# Kintex7_disp_out_hdmi.net
KiCad netlist of a schematic drawn in EAGLE
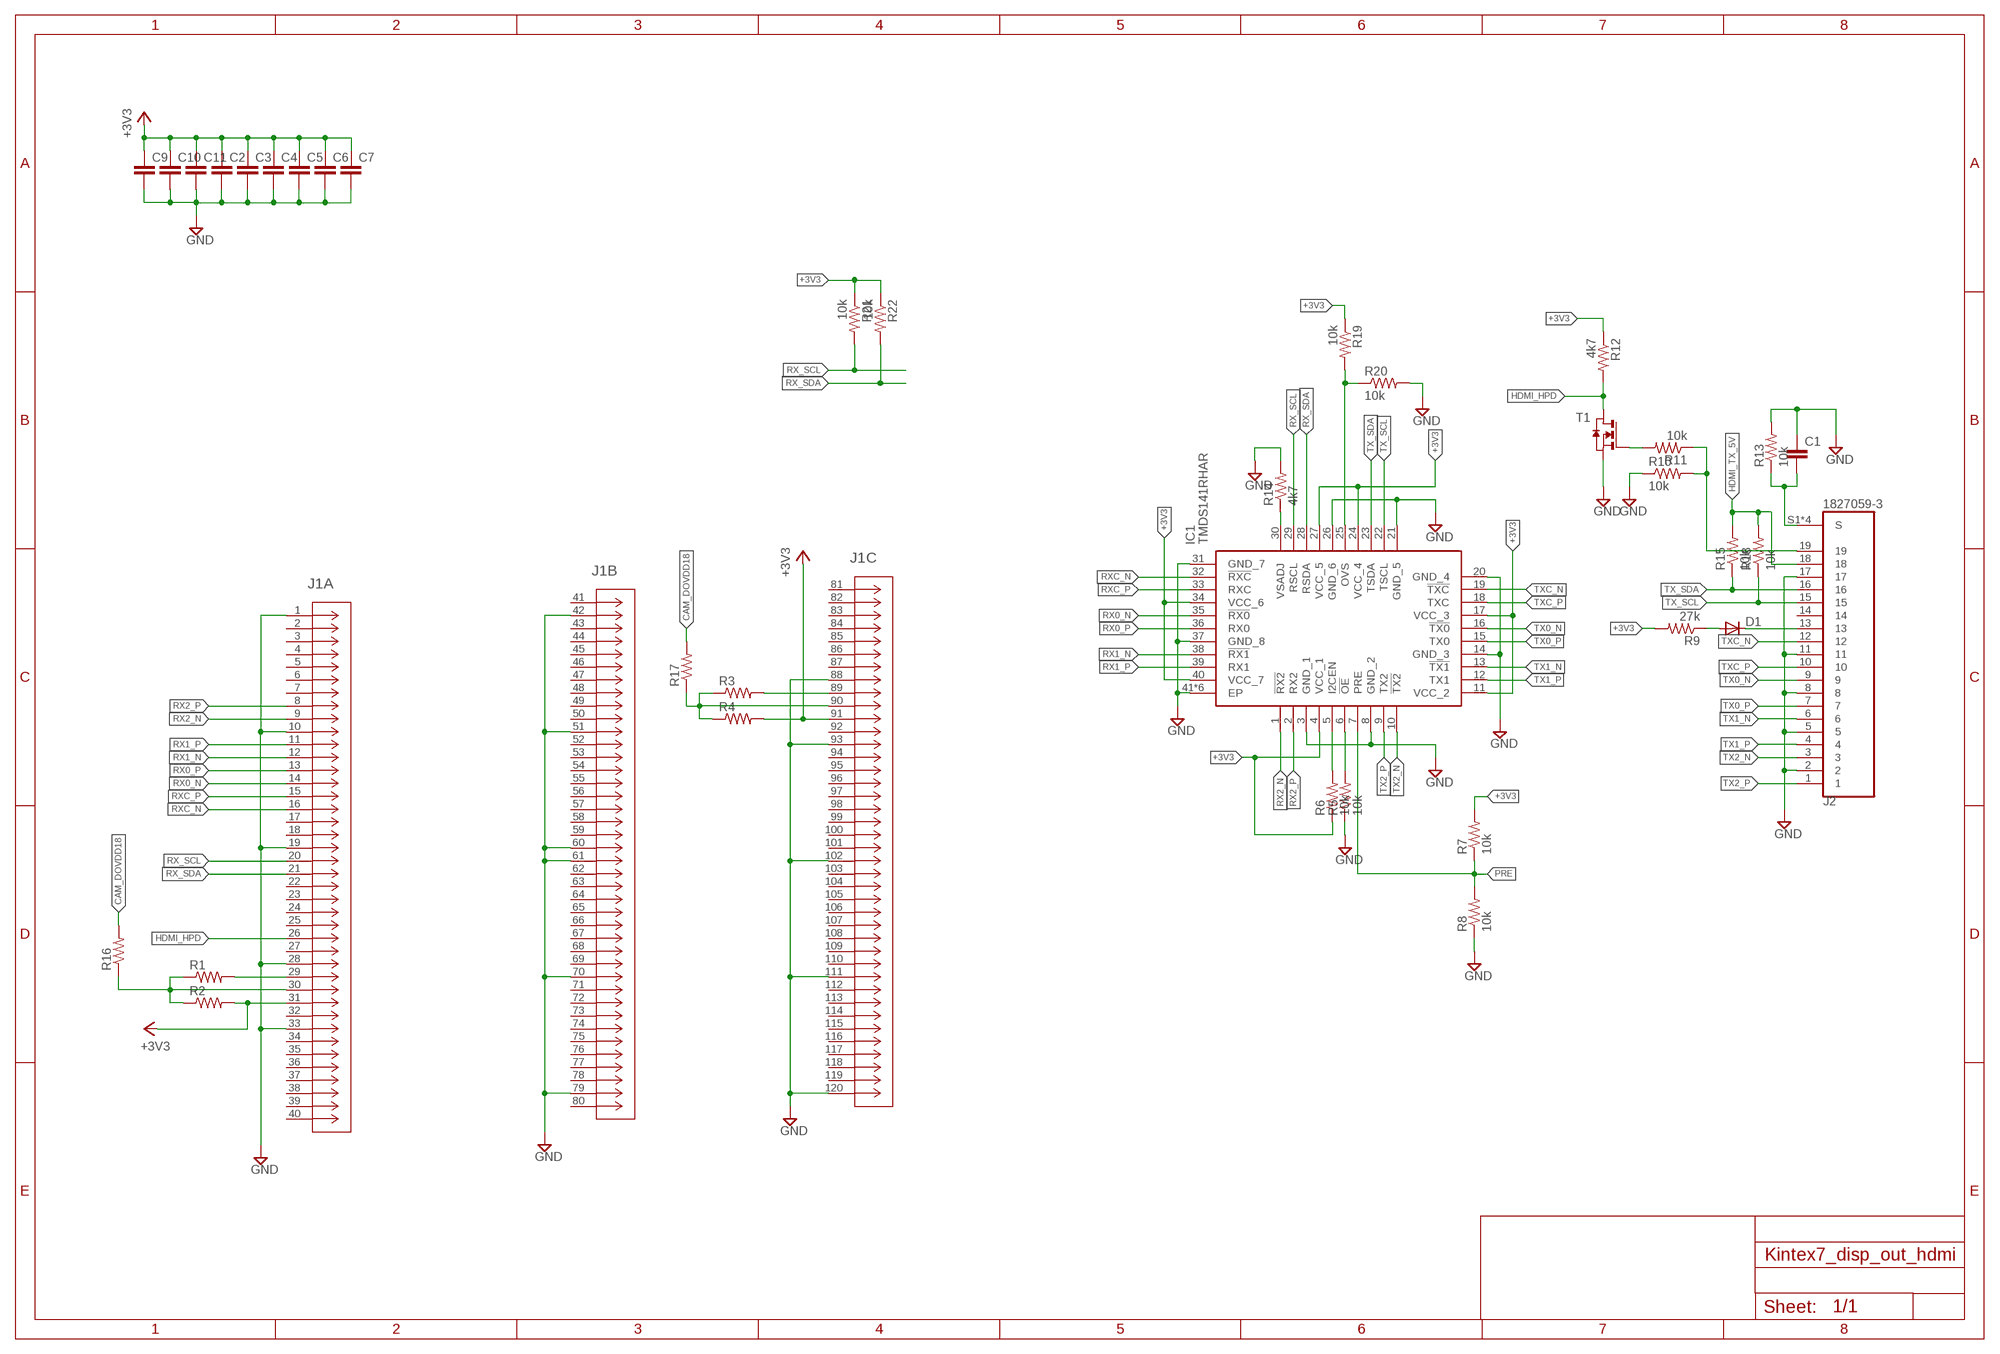
[diagram p0: schematic, sheet 1]

(export (version "E")
  (design (tool "Eeschema 10.0.6"))
  (components
    (comp (ref "C1")
      (value "C-EUC0603")
      (footprint "eagle-import:C0603")
      (libsource (lib "eagle-import") (part "C-EUC0603"))
    )
    (comp (ref "C2")
      (value "C-EUC0603")
      (footprint "eagle-import:C0603")
      (libsource (lib "eagle-import") (part "C-EUC0603"))
    )
    (comp (ref "C3")
      (value "C-EUC0603")
      (footprint "eagle-import:C0603")
      (libsource (lib "eagle-import") (part "C-EUC0603"))
    )
    (comp (ref "C4")
      (value "C-EUC0603")
      (footprint "eagle-import:C0603")
      (libsource (lib "eagle-import") (part "C-EUC0603"))
    )
    (comp (ref "C5")
      (value "C-EUC0603")
      (footprint "eagle-import:C0603")
      (libsource (lib "eagle-import") (part "C-EUC0603"))
    )
    (comp (ref "C6")
      (value "C-EUC0603")
      (footprint "eagle-import:C0603")
      (libsource (lib "eagle-import") (part "C-EUC0603"))
    )
    (comp (ref "C7")
      (value "C-EUC0603")
      (footprint "eagle-import:C0603")
      (libsource (lib "eagle-import") (part "C-EUC0603"))
    )
    (comp (ref "C9")
      (value "C-EUC0603")
      (footprint "eagle-import:C0603")
      (libsource (lib "eagle-import") (part "C-EUC0603"))
    )
    (comp (ref "C10")
      (value "C-EUC0603")
      (footprint "eagle-import:C0603")
      (libsource (lib "eagle-import") (part "C-EUC0603"))
    )
    (comp (ref "C11")
      (value "C-EUC0603")
      (footprint "eagle-import:C0603")
      (libsource (lib "eagle-import") (part "C-EUC0603"))
    )
    (comp (ref "D1")
      (value "DIODE-MINIMELF")
      (footprint "eagle-import:MINIMELF")
      (libsource (lib "eagle-import") (part "DIODE-MINIMELF"))
    )
    (comp (ref "IC1")
      (value "TMDS141RHAR")
      (footprint "eagle-import:QFN50P600X600X100-41N")
      (fields (field (name "RS_PART_NUMBER") "8124195P"))
      (libsource (lib "eagle-import") (part "TMDS141RHAR"))
    )
    (comp (ref "J1")
      (value "5177985-5")
      (footprint "eagle-import:CONN_5177985-5")
      (libsource (lib "eagle-import") (part "5177985-5"))
    )
    (comp (ref "J2")
      (value "1827059-3")
      (footprint "eagle-import:TE_1827059-3")
      (fields (field (name "MF") "TE Connectivity"))
      (libsource (lib "eagle-import") (part "1827059-3"))
    )
    (comp (ref "R1")
      (value "R-US_R0805")
      (footprint "eagle-import:R0805")
      (libsource (lib "eagle-import") (part "R-US_R0805"))
    )
    (comp (ref "R2")
      (value "R-US_R0805")
      (footprint "eagle-import:R0805")
      (libsource (lib "eagle-import") (part "R-US_R0805"))
    )
    (comp (ref "R3")
      (value "R-US_R0805")
      (footprint "eagle-import:R0805")
      (libsource (lib "eagle-import") (part "R-US_R0805"))
    )
    (comp (ref "R4")
      (value "R-US_R0805")
      (footprint "eagle-import:R0805")
      (libsource (lib "eagle-import") (part "R-US_R0805"))
    )
    (comp (ref "R5")
      (value "10k")
      (footprint "eagle-import:R0805")
      (libsource (lib "eagle-import") (part "R-US_R0805"))
    )
    (comp (ref "R6")
      (value "10k")
      (footprint "eagle-import:R0805")
      (libsource (lib "eagle-import") (part "R-US_R0805"))
    )
    (comp (ref "R7")
      (value "10k")
      (footprint "eagle-import:R0805")
      (libsource (lib "eagle-import") (part "R-US_R0805"))
    )
    (comp (ref "R8")
      (value "10k")
      (footprint "eagle-import:R0805")
      (libsource (lib "eagle-import") (part "R-US_R0805"))
    )
    (comp (ref "R9")
      (value "27k")
      (footprint "eagle-import:R0805")
      (libsource (lib "eagle-import") (part "R-US_R0805"))
    )
    (comp (ref "R10")
      (value "10k")
      (footprint "eagle-import:R0805")
      (libsource (lib "eagle-import") (part "R-US_R0805"))
    )
    (comp (ref "R11")
      (value "10k")
      (footprint "eagle-import:R0805")
      (libsource (lib "eagle-import") (part "R-US_R0805"))
    )
    (comp (ref "R12")
      (value "4k7")
      (footprint "eagle-import:R0805")
      (libsource (lib "eagle-import") (part "R-US_R0805"))
    )
    (comp (ref "R13")
      (value "10k")
      (footprint "eagle-import:R0805")
      (libsource (lib "eagle-import") (part "R-US_R0805"))
    )
    (comp (ref "R14")
      (value "4k7")
      (footprint "eagle-import:R0805")
      (libsource (lib "eagle-import") (part "R-US_R0805"))
    )
    (comp (ref "R15")
      (value "10k")
      (footprint "eagle-import:R0805")
      (libsource (lib "eagle-import") (part "R-US_R0805"))
    )
    (comp (ref "R16")
      (value "R-US_R0805")
      (footprint "eagle-import:R0805")
      (libsource (lib "eagle-import") (part "R-US_R0805"))
    )
    (comp (ref "R17")
      (value "R-US_R0805")
      (footprint "eagle-import:R0805")
      (libsource (lib "eagle-import") (part "R-US_R0805"))
    )
    (comp (ref "R18")
      (value "10k")
      (footprint "eagle-import:R0805")
      (libsource (lib "eagle-import") (part "R-US_R0805"))
    )
    (comp (ref "R19")
      (value "10k")
      (footprint "eagle-import:R0805")
      (libsource (lib "eagle-import") (part "R-US_R0805"))
    )
    (comp (ref "R20")
      (value "10k")
      (footprint "eagle-import:R0805")
      (libsource (lib "eagle-import") (part "R-US_R0805"))
    )
    (comp (ref "R21")
      (value "10k")
      (footprint "eagle-import:R0805")
      (libsource (lib "eagle-import") (part "R-US_R0805"))
    )
    (comp (ref "R22")
      (value "10k")
      (footprint "eagle-import:R0805")
      (libsource (lib "eagle-import") (part "R-US_R0805"))
    )
    (comp (ref "T1")
      (value "NMOSSOT23")
      (footprint "eagle-import:SOT-23")
      (libsource (lib "eagle-import") (part "NMOSSOT23"))
    )
  )
  (nets
    (net (code "1") (name "+3V3") (class "Default")
      (node (ref "C10") (pin "1") (pinfunction "1_1") (pintype "passive"))
      (node (ref "C11") (pin "1") (pinfunction "1_1") (pintype "passive"))
      (node (ref "C2") (pin "1") (pinfunction "1_1") (pintype "passive"))
      (node (ref "C3") (pin "1") (pinfunction "1_1") (pintype "passive"))
      (node (ref "C4") (pin "1") (pinfunction "1_1") (pintype "passive"))
      (node (ref "C5") (pin "1") (pinfunction "1_1") (pintype "passive"))
      (node (ref "C6") (pin "1") (pinfunction "1_1") (pintype "passive"))
      (node (ref "C7") (pin "1") (pinfunction "1_1") (pintype "passive"))
      (node (ref "C9") (pin "1") (pinfunction "1_1") (pintype "passive"))
      (node (ref "IC1") (pin "11") (pinfunction "VCC_2_11") (pintype "bidirectional"))
      (node (ref "IC1") (pin "17") (pinfunction "VCC_3_17") (pintype "bidirectional"))
      (node (ref "IC1") (pin "24") (pinfunction "VCC_4_24") (pintype "bidirectional"))
      (node (ref "IC1") (pin "27") (pinfunction "VCC_5_27") (pintype "bidirectional"))
      (node (ref "IC1") (pin "34") (pinfunction "VCC_6_34") (pintype "bidirectional"))
      (node (ref "IC1") (pin "4") (pinfunction "VCC_1_4") (pintype "bidirectional"))
      (node (ref "IC1") (pin "40") (pinfunction "VCC_7_40") (pintype "bidirectional"))
      (node (ref "J1") (pin "31") (pinfunction "31_31") (pintype "passive"))
      (node (ref "J1") (pin "91") (pinfunction "91_91") (pintype "passive"))
      (node (ref "R12") (pin "1") (pinfunction "1_1") (pintype "passive"))
      (node (ref "R19") (pin "1") (pinfunction "1_1") (pintype "passive"))
      (node (ref "R2") (pin "2") (pinfunction "2_2") (pintype "passive"))
      (node (ref "R21") (pin "1") (pinfunction "1_1") (pintype "passive"))
      (node (ref "R22") (pin "1") (pinfunction "1_1") (pintype "passive"))
      (node (ref "R4") (pin "2") (pinfunction "2_2") (pintype "passive"))
      (node (ref "R6") (pin "1") (pinfunction "1_1") (pintype "passive"))
      (node (ref "R7") (pin "2") (pinfunction "2_2") (pintype "passive"))
      (node (ref "R9") (pin "2") (pinfunction "2_2") (pintype "passive"))
    )
    (net (code "2") (name "CAM_DOVDD18") (class "Default")
      (node (ref "R16") (pin "2") (pinfunction "2_2") (pintype "passive"))
      (node (ref "R17") (pin "2") (pinfunction "2_2") (pintype "passive"))
    )
    (net (code "3") (name "GND") (class "Default")
      (node (ref "C1") (pin "1") (pinfunction "1_1") (pintype "passive"))
      (node (ref "C10") (pin "2") (pinfunction "2_2") (pintype "passive"))
      (node (ref "C11") (pin "2") (pinfunction "2_2") (pintype "passive"))
      (node (ref "C2") (pin "2") (pinfunction "2_2") (pintype "passive"))
      (node (ref "C3") (pin "2") (pinfunction "2_2") (pintype "passive"))
      (node (ref "C4") (pin "2") (pinfunction "2_2") (pintype "passive"))
      (node (ref "C5") (pin "2") (pinfunction "2_2") (pintype "passive"))
      (node (ref "C6") (pin "2") (pinfunction "2_2") (pintype "passive"))
      (node (ref "C7") (pin "2") (pinfunction "2_2") (pintype "passive"))
      (node (ref "C9") (pin "2") (pinfunction "2_2") (pintype "passive"))
      (node (ref "IC1") (pin "14") (pinfunction "GND_3_14") (pintype "bidirectional"))
      (node (ref "IC1") (pin "20") (pinfunction "GND_4_20") (pintype "bidirectional"))
      (node (ref "IC1") (pin "21") (pinfunction "GND_5_21") (pintype "bidirectional"))
      (node (ref "IC1") (pin "26") (pinfunction "GND_6_26") (pintype "bidirectional"))
      (node (ref "IC1") (pin "3") (pinfunction "GND_1_3") (pintype "bidirectional"))
      (node (ref "IC1") (pin "31") (pinfunction "GND_7_31") (pintype "bidirectional"))
      (node (ref "IC1") (pin "37") (pinfunction "GND_8_37") (pintype "bidirectional"))
      (node (ref "IC1") (pin "41") (pinfunction "EP_41") (pintype "bidirectional"))
      (node (ref "IC1") (pin "8") (pinfunction "GND_2_8") (pintype "bidirectional"))
      (node (ref "IC1") (pin "P$1") (pinfunction "EP_P$1") (pintype "bidirectional"))
      (node (ref "IC1") (pin "P$2") (pinfunction "EP_P$2") (pintype "bidirectional"))
      (node (ref "IC1") (pin "P$3") (pinfunction "EP_P$3") (pintype "bidirectional"))
      (node (ref "IC1") (pin "P$4") (pinfunction "EP_P$4") (pintype "bidirectional"))
      (node (ref "IC1") (pin "P$5") (pinfunction "EP_P$5") (pintype "bidirectional"))
      (node (ref "J1") (pin "1") (pinfunction "1_1") (pintype "passive"))
      (node (ref "J1") (pin "10") (pinfunction "10_10") (pintype "passive"))
      (node (ref "J1") (pin "102") (pinfunction "102_102") (pintype "passive"))
      (node (ref "J1") (pin "111") (pinfunction "111_111") (pintype "passive"))
      (node (ref "J1") (pin "120") (pinfunction "120_120") (pintype "passive"))
      (node (ref "J1") (pin "19") (pinfunction "19_19") (pintype "passive"))
      (node (ref "J1") (pin "28") (pinfunction "28_28") (pintype "passive"))
      (node (ref "J1") (pin "33") (pinfunction "33_33") (pintype "passive"))
      (node (ref "J1") (pin "42") (pinfunction "42_42") (pintype "passive"))
      (node (ref "J1") (pin "51") (pinfunction "51_51") (pintype "passive"))
      (node (ref "J1") (pin "60") (pinfunction "60_60") (pintype "passive"))
      (node (ref "J1") (pin "61") (pinfunction "61_61") (pintype "passive"))
      (node (ref "J1") (pin "70") (pinfunction "70_70") (pintype "passive"))
      (node (ref "J1") (pin "79") (pinfunction "79_79") (pintype "passive"))
      (node (ref "J1") (pin "88") (pinfunction "88_88") (pintype "passive"))
      (node (ref "J1") (pin "93") (pinfunction "93_93") (pintype "passive"))
      (node (ref "J2") (pin "11") (pinfunction "11_11") (pintype "passive"))
      (node (ref "J2") (pin "17") (pinfunction "17_17") (pintype "passive"))
      (node (ref "J2") (pin "2") (pinfunction "2_2") (pintype "passive"))
      (node (ref "J2") (pin "5") (pinfunction "5_5") (pintype "passive"))
      (node (ref "J2") (pin "8") (pinfunction "8_8") (pintype "passive"))
      (node (ref "R10") (pin "1") (pinfunction "1_1") (pintype "passive"))
      (node (ref "R13") (pin "2") (pinfunction "2_2") (pintype "passive"))
      (node (ref "R14") (pin "2") (pinfunction "2_2") (pintype "passive"))
      (node (ref "R20") (pin "2") (pinfunction "2_2") (pintype "passive"))
      (node (ref "R5") (pin "1") (pinfunction "1_1") (pintype "passive"))
      (node (ref "R8") (pin "1") (pinfunction "1_1") (pintype "passive"))
      (node (ref "T1") (pin "2") (pinfunction "S_2") (pintype "passive"))
    )
    (net (code "4") (name "HDMI_HPD") (class "Default")
      (node (ref "J1") (pin "26") (pinfunction "26_26") (pintype "passive"))
      (node (ref "R12") (pin "2") (pinfunction "2_2") (pintype "passive"))
      (node (ref "T1") (pin "1") (pinfunction "D_1") (pintype "passive"))
    )
    (net (code "5") (name "HDMI_TX_5V") (class "Default")
      (node (ref "J2") (pin "18") (pinfunction "18_18") (pintype "passive"))
      (node (ref "R15") (pin "2") (pinfunction "2_2") (pintype "passive"))
      (node (ref "R18") (pin "2") (pinfunction "2_2") (pintype "passive"))
    )
    (net (code "6") (name "Net-(C1-Pad2)") (class "Default")
      (node (ref "C1") (pin "2") (pinfunction "2_2") (pintype "passive"))
      (node (ref "J2") (pin "S1") (pinfunction "S_S1") (pintype "passive"))
      (node (ref "J2") (pin "S2") (pinfunction "S_S2") (pintype "passive"))
      (node (ref "J2") (pin "S3") (pinfunction "S_S3") (pintype "passive"))
      (node (ref "J2") (pin "S4") (pinfunction "S_S4") (pintype "passive"))
      (node (ref "R13") (pin "1") (pinfunction "1_1") (pintype "passive"))
    )
    (net (code "7") (name "Net-(D1-PadA)") (class "Default")
      (node (ref "D1") (pin "A") (pinfunction "A_A") (pintype "passive"))
      (node (ref "R9") (pin "1") (pinfunction "1_1") (pintype "passive"))
    )
    (net (code "8") (name "Net-(D1-PadC)") (class "Default")
      (node (ref "D1") (pin "C") (pinfunction "C_C") (pintype "passive"))
      (node (ref "J2") (pin "13") (pinfunction "13_13") (pintype "passive"))
    )
    (net (code "9") (name "Net-(IC1-I2CEN)") (class "Default")
      (node (ref "IC1") (pin "5") (pinfunction "I2CEN_5") (pintype "bidirectional"))
      (node (ref "R6") (pin "2") (pinfunction "2_2") (pintype "passive"))
    )
    (net (code "10") (name "Net-(IC1-OVS)") (class "Default")
      (node (ref "IC1") (pin "25") (pinfunction "OVS_25") (pintype "bidirectional"))
      (node (ref "R19") (pin "2") (pinfunction "2_2") (pintype "passive"))
      (node (ref "R20") (pin "1") (pinfunction "1_1") (pintype "passive"))
    )
    (net (code "11") (name "Net-(IC1-VSADJ)") (class "Default")
      (node (ref "IC1") (pin "30") (pinfunction "VSADJ_30") (pintype "bidirectional"))
      (node (ref "R14") (pin "1") (pinfunction "1_1") (pintype "passive"))
    )
    (net (code "12") (name "Net-(IC1-~{OE})") (class "Default")
      (node (ref "IC1") (pin "6") (pinfunction "~{OE}_6") (pintype "bidirectional"))
      (node (ref "R5") (pin "2") (pinfunction "2_2") (pintype "passive"))
    )
    (net (code "13") (name "Net-(J1-Pad29)") (class "Default")
      (node (ref "J1") (pin "29") (pinfunction "29_29") (pintype "passive"))
      (node (ref "R1") (pin "2") (pinfunction "2_2") (pintype "passive"))
    )
    (net (code "14") (name "Net-(J1-Pad30)") (class "Default")
      (node (ref "J1") (pin "30") (pinfunction "30_30") (pintype "passive"))
      (node (ref "R1") (pin "1") (pinfunction "1_1") (pintype "passive"))
      (node (ref "R16") (pin "1") (pinfunction "1_1") (pintype "passive"))
      (node (ref "R2") (pin "1") (pinfunction "1_1") (pintype "passive"))
    )
    (net (code "15") (name "Net-(J1-Pad89)") (class "Default")
      (node (ref "J1") (pin "89") (pinfunction "89_89") (pintype "passive"))
      (node (ref "R3") (pin "2") (pinfunction "2_2") (pintype "passive"))
    )
    (net (code "16") (name "Net-(J1-Pad90)") (class "Default")
      (node (ref "J1") (pin "90") (pinfunction "90_90") (pintype "passive"))
      (node (ref "R17") (pin "1") (pinfunction "1_1") (pintype "passive"))
      (node (ref "R3") (pin "1") (pinfunction "1_1") (pintype "passive"))
      (node (ref "R4") (pin "1") (pinfunction "1_1") (pintype "passive"))
    )
    (net (code "17") (name "Net-(J2-Pad19)") (class "Default")
      (node (ref "J2") (pin "19") (pinfunction "19_19") (pintype "passive"))
      (node (ref "R10") (pin "2") (pinfunction "2_2") (pintype "passive"))
      (node (ref "R11") (pin "1") (pinfunction "1_1") (pintype "passive"))
    )
    (net (code "18") (name "Net-(T1-G)") (class "Default")
      (node (ref "R11") (pin "2") (pinfunction "2_2") (pintype "passive"))
      (node (ref "T1") (pin "3") (pinfunction "G_3") (pintype "passive"))
    )
    (net (code "19") (name "PRE") (class "Default")
      (node (ref "IC1") (pin "7") (pinfunction "PRE_7") (pintype "bidirectional"))
      (node (ref "R7") (pin "1") (pinfunction "1_1") (pintype "passive"))
      (node (ref "R8") (pin "2") (pinfunction "2_2") (pintype "passive"))
    )
    (net (code "20") (name "RX0_N") (class "Default")
      (node (ref "IC1") (pin "35") (pinfunction "~{RX0}_35") (pintype "bidirectional"))
      (node (ref "J1") (pin "14") (pinfunction "14_14") (pintype "passive"))
    )
    (net (code "21") (name "RX0_P") (class "Default")
      (node (ref "IC1") (pin "36") (pinfunction "RX0_36") (pintype "bidirectional"))
      (node (ref "J1") (pin "13") (pinfunction "13_13") (pintype "passive"))
    )
    (net (code "22") (name "RX1_N") (class "Default")
      (node (ref "IC1") (pin "38") (pinfunction "~{RX1}_38") (pintype "bidirectional"))
      (node (ref "J1") (pin "12") (pinfunction "12_12") (pintype "passive"))
    )
    (net (code "23") (name "RX1_P") (class "Default")
      (node (ref "IC1") (pin "39") (pinfunction "RX1_39") (pintype "bidirectional"))
      (node (ref "J1") (pin "11") (pinfunction "11_11") (pintype "passive"))
    )
    (net (code "24") (name "RX2_N") (class "Default")
      (node (ref "IC1") (pin "1") (pinfunction "~{RX2}_1") (pintype "bidirectional"))
      (node (ref "J1") (pin "9") (pinfunction "9_9") (pintype "passive"))
    )
    (net (code "25") (name "RX2_P") (class "Default")
      (node (ref "IC1") (pin "2") (pinfunction "RX2_2") (pintype "bidirectional"))
      (node (ref "J1") (pin "8") (pinfunction "8_8") (pintype "passive"))
    )
    (net (code "26") (name "RXC_N") (class "Default")
      (node (ref "IC1") (pin "32") (pinfunction "~{RXC}_32") (pintype "bidirectional"))
      (node (ref "J1") (pin "16") (pinfunction "16_16") (pintype "passive"))
    )
    (net (code "27") (name "RXC_P") (class "Default")
      (node (ref "IC1") (pin "33") (pinfunction "RXC_33") (pintype "bidirectional"))
      (node (ref "J1") (pin "15") (pinfunction "15_15") (pintype "passive"))
    )
    (net (code "28") (name "RX_SCL") (class "Default")
      (node (ref "IC1") (pin "29") (pinfunction "RSCL_29") (pintype "bidirectional"))
      (node (ref "J1") (pin "20") (pinfunction "20_20") (pintype "passive"))
      (node (ref "R21") (pin "2") (pinfunction "2_2") (pintype "passive"))
    )
    (net (code "29") (name "RX_SDA") (class "Default")
      (node (ref "IC1") (pin "28") (pinfunction "RSDA_28") (pintype "bidirectional"))
      (node (ref "J1") (pin "21") (pinfunction "21_21") (pintype "passive"))
      (node (ref "R22") (pin "2") (pinfunction "2_2") (pintype "passive"))
    )
    (net (code "30") (name "TX0_N") (class "Default")
      (node (ref "IC1") (pin "16") (pinfunction "~{TX0}_16") (pintype "bidirectional"))
      (node (ref "J2") (pin "9") (pinfunction "9_9") (pintype "passive"))
    )
    (net (code "31") (name "TX0_P") (class "Default")
      (node (ref "IC1") (pin "15") (pinfunction "TX0_15") (pintype "bidirectional"))
      (node (ref "J2") (pin "7") (pinfunction "7_7") (pintype "passive"))
    )
    (net (code "32") (name "TX1_N") (class "Default")
      (node (ref "IC1") (pin "13") (pinfunction "~{TX1}_13") (pintype "bidirectional"))
      (node (ref "J2") (pin "6") (pinfunction "6_6") (pintype "passive"))
    )
    (net (code "33") (name "TX1_P") (class "Default")
      (node (ref "IC1") (pin "12") (pinfunction "TX1_12") (pintype "bidirectional"))
      (node (ref "J2") (pin "4") (pinfunction "4_4") (pintype "passive"))
    )
    (net (code "34") (name "TX2_N") (class "Default")
      (node (ref "IC1") (pin "10") (pinfunction "~{TX2}_10") (pintype "bidirectional"))
      (node (ref "J2") (pin "3") (pinfunction "3_3") (pintype "passive"))
    )
    (net (code "35") (name "TX2_P") (class "Default")
      (node (ref "IC1") (pin "9") (pinfunction "TX2_9") (pintype "bidirectional"))
      (node (ref "J2") (pin "1") (pinfunction "1_1") (pintype "passive"))
    )
    (net (code "36") (name "TXC_N") (class "Default")
      (node (ref "IC1") (pin "19") (pinfunction "~{TXC}_19") (pintype "bidirectional"))
      (node (ref "J2") (pin "12") (pinfunction "12_12") (pintype "passive"))
    )
    (net (code "37") (name "TXC_P") (class "Default")
      (node (ref "IC1") (pin "18") (pinfunction "TXC_18") (pintype "bidirectional"))
      (node (ref "J2") (pin "10") (pinfunction "10_10") (pintype "passive"))
    )
    (net (code "38") (name "TX_SCL") (class "Default")
      (node (ref "IC1") (pin "22") (pinfunction "TSCL_22") (pintype "bidirectional"))
      (node (ref "J2") (pin "15") (pinfunction "15_15") (pintype "passive"))
      (node (ref "R18") (pin "1") (pinfunction "1_1") (pintype "passive"))
    )
    (net (code "39") (name "TX_SDA") (class "Default")
      (node (ref "IC1") (pin "23") (pinfunction "TSDA_23") (pintype "bidirectional"))
      (node (ref "J2") (pin "16") (pinfunction "16_16") (pintype "passive"))
      (node (ref "R15") (pin "1") (pinfunction "1_1") (pintype "passive"))
    )
    (net (code "40") (name "unconnected-(J1-Pad2)") (class "Default")
      (node (ref "J1") (pin "2") (pinfunction "2_2") (pintype "passive"))
    )
    (net (code "41") (name "unconnected-(J1-Pad3)") (class "Default")
      (node (ref "J1") (pin "3") (pinfunction "3_3") (pintype "passive"))
    )
    (net (code "42") (name "unconnected-(J1-Pad4)") (class "Default")
      (node (ref "J1") (pin "4") (pinfunction "4_4") (pintype "passive"))
    )
    (net (code "43") (name "unconnected-(J1-Pad5)") (class "Default")
      (node (ref "J1") (pin "5") (pinfunction "5_5") (pintype "passive"))
    )
    (net (code "44") (name "unconnected-(J1-Pad6)") (class "Default")
      (node (ref "J1") (pin "6") (pinfunction "6_6") (pintype "passive"))
    )
    (net (code "45") (name "unconnected-(J1-Pad7)") (class "Default")
      (node (ref "J1") (pin "7") (pinfunction "7_7") (pintype "passive"))
    )
    (net (code "46") (name "unconnected-(J1-Pad17)") (class "Default")
      (node (ref "J1") (pin "17") (pinfunction "17_17") (pintype "passive"))
    )
    (net (code "47") (name "unconnected-(J1-Pad18)") (class "Default")
      (node (ref "J1") (pin "18") (pinfunction "18_18") (pintype "passive"))
    )
    (net (code "48") (name "unconnected-(J1-Pad22)") (class "Default")
      (node (ref "J1") (pin "22") (pinfunction "22_22") (pintype "passive"))
    )
    (net (code "49") (name "unconnected-(J1-Pad23)") (class "Default")
      (node (ref "J1") (pin "23") (pinfunction "23_23") (pintype "passive"))
    )
    (net (code "50") (name "unconnected-(J1-Pad24)") (class "Default")
      (node (ref "J1") (pin "24") (pinfunction "24_24") (pintype "passive"))
    )
    (net (code "51") (name "unconnected-(J1-Pad25)") (class "Default")
      (node (ref "J1") (pin "25") (pinfunction "25_25") (pintype "passive"))
    )
    (net (code "52") (name "unconnected-(J1-Pad27)") (class "Default")
      (node (ref "J1") (pin "27") (pinfunction "27_27") (pintype "passive"))
    )
    (net (code "53") (name "unconnected-(J1-Pad32)") (class "Default")
      (node (ref "J1") (pin "32") (pinfunction "32_32") (pintype "passive"))
    )
    (net (code "54") (name "unconnected-(J1-Pad34)") (class "Default")
      (node (ref "J1") (pin "34") (pinfunction "34_34") (pintype "passive"))
    )
    (net (code "55") (name "unconnected-(J1-Pad35)") (class "Default")
      (node (ref "J1") (pin "35") (pinfunction "35_35") (pintype "passive"))
    )
    (net (code "56") (name "unconnected-(J1-Pad36)") (class "Default")
      (node (ref "J1") (pin "36") (pinfunction "36_36") (pintype "passive"))
    )
    (net (code "57") (name "unconnected-(J1-Pad37)") (class "Default")
      (node (ref "J1") (pin "37") (pinfunction "37_37") (pintype "passive"))
    )
    (net (code "58") (name "unconnected-(J1-Pad38)") (class "Default")
      (node (ref "J1") (pin "38") (pinfunction "38_38") (pintype "passive"))
    )
    (net (code "59") (name "unconnected-(J1-Pad39)") (class "Default")
      (node (ref "J1") (pin "39") (pinfunction "39_39") (pintype "passive"))
    )
    (net (code "60") (name "unconnected-(J1-Pad40)") (class "Default")
      (node (ref "J1") (pin "40") (pinfunction "40_40") (pintype "passive"))
    )
    (net (code "61") (name "unconnected-(J1-Pad41)") (class "Default")
      (node (ref "J1") (pin "41") (pinfunction "41_41") (pintype "passive"))
    )
    (net (code "62") (name "unconnected-(J1-Pad43)") (class "Default")
      (node (ref "J1") (pin "43") (pinfunction "43_43") (pintype "passive"))
    )
    (net (code "63") (name "unconnected-(J1-Pad44)") (class "Default")
      (node (ref "J1") (pin "44") (pinfunction "44_44") (pintype "passive"))
    )
    (net (code "64") (name "unconnected-(J1-Pad45)") (class "Default")
      (node (ref "J1") (pin "45") (pinfunction "45_45") (pintype "passive"))
    )
    (net (code "65") (name "unconnected-(J1-Pad46)") (class "Default")
      (node (ref "J1") (pin "46") (pinfunction "46_46") (pintype "passive"))
    )
    (net (code "66") (name "unconnected-(J1-Pad47)") (class "Default")
      (node (ref "J1") (pin "47") (pinfunction "47_47") (pintype "passive"))
    )
    (net (code "67") (name "unconnected-(J1-Pad48)") (class "Default")
      (node (ref "J1") (pin "48") (pinfunction "48_48") (pintype "passive"))
    )
    (net (code "68") (name "unconnected-(J1-Pad49)") (class "Default")
      (node (ref "J1") (pin "49") (pinfunction "49_49") (pintype "passive"))
    )
    (net (code "69") (name "unconnected-(J1-Pad50)") (class "Default")
      (node (ref "J1") (pin "50") (pinfunction "50_50") (pintype "passive"))
    )
    (net (code "70") (name "unconnected-(J1-Pad52)") (class "Default")
      (node (ref "J1") (pin "52") (pinfunction "52_52") (pintype "passive"))
    )
    (net (code "71") (name "unconnected-(J1-Pad53)") (class "Default")
      (node (ref "J1") (pin "53") (pinfunction "53_53") (pintype "passive"))
    )
    (net (code "72") (name "unconnected-(J1-Pad54)") (class "Default")
      (node (ref "J1") (pin "54") (pinfunction "54_54") (pintype "passive"))
    )
    (net (code "73") (name "unconnected-(J1-Pad55)") (class "Default")
      (node (ref "J1") (pin "55") (pinfunction "55_55") (pintype "passive"))
    )
    (net (code "74") (name "unconnected-(J1-Pad56)") (class "Default")
      (node (ref "J1") (pin "56") (pinfunction "56_56") (pintype "passive"))
    )
    (net (code "75") (name "unconnected-(J1-Pad57)") (class "Default")
      (node (ref "J1") (pin "57") (pinfunction "57_57") (pintype "passive"))
    )
    (net (code "76") (name "unconnected-(J1-Pad58)") (class "Default")
      (node (ref "J1") (pin "58") (pinfunction "58_58") (pintype "passive"))
    )
    (net (code "77") (name "unconnected-(J1-Pad59)") (class "Default")
      (node (ref "J1") (pin "59") (pinfunction "59_59") (pintype "passive"))
    )
    (net (code "78") (name "unconnected-(J1-Pad62)") (class "Default")
      (node (ref "J1") (pin "62") (pinfunction "62_62") (pintype "passive"))
    )
    (net (code "79") (name "unconnected-(J1-Pad63)") (class "Default")
      (node (ref "J1") (pin "63") (pinfunction "63_63") (pintype "passive"))
    )
    (net (code "80") (name "unconnected-(J1-Pad64)") (class "Default")
      (node (ref "J1") (pin "64") (pinfunction "64_64") (pintype "passive"))
    )
    (net (code "81") (name "unconnected-(J1-Pad65)") (class "Default")
      (node (ref "J1") (pin "65") (pinfunction "65_65") (pintype "passive"))
    )
    (net (code "82") (name "unconnected-(J1-Pad66)") (class "Default")
      (node (ref "J1") (pin "66") (pinfunction "66_66") (pintype "passive"))
    )
    (net (code "83") (name "unconnected-(J1-Pad67)") (class "Default")
      (node (ref "J1") (pin "67") (pinfunction "67_67") (pintype "passive"))
    )
    (net (code "84") (name "unconnected-(J1-Pad68)") (class "Default")
      (node (ref "J1") (pin "68") (pinfunction "68_68") (pintype "passive"))
    )
    (net (code "85") (name "unconnected-(J1-Pad69)") (class "Default")
      (node (ref "J1") (pin "69") (pinfunction "69_69") (pintype "passive"))
    )
    (net (code "86") (name "unconnected-(J1-Pad71)") (class "Default")
      (node (ref "J1") (pin "71") (pinfunction "71_71") (pintype "passive"))
    )
    (net (code "87") (name "unconnected-(J1-Pad72)") (class "Default")
      (node (ref "J1") (pin "72") (pinfunction "72_72") (pintype "passive"))
    )
    (net (code "88") (name "unconnected-(J1-Pad73)") (class "Default")
      (node (ref "J1") (pin "73") (pinfunction "73_73") (pintype "passive"))
    )
    (net (code "89") (name "unconnected-(J1-Pad74)") (class "Default")
      (node (ref "J1") (pin "74") (pinfunction "74_74") (pintype "passive"))
    )
    (net (code "90") (name "unconnected-(J1-Pad75)") (class "Default")
      (node (ref "J1") (pin "75") (pinfunction "75_75") (pintype "passive"))
    )
    (net (code "91") (name "unconnected-(J1-Pad76)") (class "Default")
      (node (ref "J1") (pin "76") (pinfunction "76_76") (pintype "passive"))
    )
    (net (code "92") (name "unconnected-(J1-Pad77)") (class "Default")
      (node (ref "J1") (pin "77") (pinfunction "77_77") (pintype "passive"))
    )
    (net (code "93") (name "unconnected-(J1-Pad78)") (class "Default")
      (node (ref "J1") (pin "78") (pinfunction "78_78") (pintype "passive"))
    )
    (net (code "94") (name "unconnected-(J1-Pad80)") (class "Default")
      (node (ref "J1") (pin "80") (pinfunction "80_80") (pintype "passive"))
    )
    (net (code "95") (name "unconnected-(J1-Pad81)") (class "Default")
      (node (ref "J1") (pin "81") (pinfunction "81_81") (pintype "passive"))
    )
    (net (code "96") (name "unconnected-(J1-Pad82)") (class "Default")
      (node (ref "J1") (pin "82") (pinfunction "82_82") (pintype "passive"))
    )
    (net (code "97") (name "unconnected-(J1-Pad83)") (class "Default")
      (node (ref "J1") (pin "83") (pinfunction "83_83") (pintype "passive"))
    )
    (net (code "98") (name "unconnected-(J1-Pad84)") (class "Default")
      (node (ref "J1") (pin "84") (pinfunction "84_84") (pintype "passive"))
    )
    (net (code "99") (name "unconnected-(J1-Pad85)") (class "Default")
      (node (ref "J1") (pin "85") (pinfunction "85_85") (pintype "passive"))
    )
    (net (code "100") (name "unconnected-(J1-Pad86)") (class "Default")
      (node (ref "J1") (pin "86") (pinfunction "86_86") (pintype "passive"))
    )
    (net (code "101") (name "unconnected-(J1-Pad87)") (class "Default")
      (node (ref "J1") (pin "87") (pinfunction "87_87") (pintype "passive"))
    )
    (net (code "102") (name "unconnected-(J1-Pad92)") (class "Default")
      (node (ref "J1") (pin "92") (pinfunction "92_92") (pintype "passive"))
    )
    (net (code "103") (name "unconnected-(J1-Pad94)") (class "Default")
      (node (ref "J1") (pin "94") (pinfunction "94_94") (pintype "passive"))
    )
    (net (code "104") (name "unconnected-(J1-Pad95)") (class "Default")
      (node (ref "J1") (pin "95") (pinfunction "95_95") (pintype "passive"))
    )
    (net (code "105") (name "unconnected-(J1-Pad96)") (class "Default")
      (node (ref "J1") (pin "96") (pinfunction "96_96") (pintype "passive"))
    )
    (net (code "106") (name "unconnected-(J1-Pad97)") (class "Default")
      (node (ref "J1") (pin "97") (pinfunction "97_97") (pintype "passive"))
    )
    (net (code "107") (name "unconnected-(J1-Pad98)") (class "Default")
      (node (ref "J1") (pin "98") (pinfunction "98_98") (pintype "passive"))
    )
    (net (code "108") (name "unconnected-(J1-Pad99)") (class "Default")
      (node (ref "J1") (pin "99") (pinfunction "99_99") (pintype "passive"))
    )
    (net (code "109") (name "unconnected-(J1-Pad100)") (class "Default")
      (node (ref "J1") (pin "100") (pinfunction "100_100") (pintype "passive"))
    )
    (net (code "110") (name "unconnected-(J1-Pad101)") (class "Default")
      (node (ref "J1") (pin "101") (pinfunction "101_101") (pintype "passive"))
    )
    (net (code "111") (name "unconnected-(J1-Pad103)") (class "Default")
      (node (ref "J1") (pin "103") (pinfunction "103_103") (pintype "passive"))
    )
    (net (code "112") (name "unconnected-(J1-Pad104)") (class "Default")
      (node (ref "J1") (pin "104") (pinfunction "104_104") (pintype "passive"))
    )
    (net (code "113") (name "unconnected-(J1-Pad105)") (class "Default")
      (node (ref "J1") (pin "105") (pinfunction "105_105") (pintype "passive"))
    )
    (net (code "114") (name "unconnected-(J1-Pad106)") (class "Default")
      (node (ref "J1") (pin "106") (pinfunction "106_106") (pintype "passive"))
    )
    (net (code "115") (name "unconnected-(J1-Pad107)") (class "Default")
      (node (ref "J1") (pin "107") (pinfunction "107_107") (pintype "passive"))
    )
    (net (code "116") (name "unconnected-(J1-Pad108)") (class "Default")
      (node (ref "J1") (pin "108") (pinfunction "108_108") (pintype "passive"))
    )
    (net (code "117") (name "unconnected-(J1-Pad109)") (class "Default")
      (node (ref "J1") (pin "109") (pinfunction "109_109") (pintype "passive"))
    )
    (net (code "118") (name "unconnected-(J1-Pad110)") (class "Default")
      (node (ref "J1") (pin "110") (pinfunction "110_110") (pintype "passive"))
    )
    (net (code "119") (name "unconnected-(J1-Pad112)") (class "Default")
      (node (ref "J1") (pin "112") (pinfunction "112_112") (pintype "passive"))
    )
    (net (code "120") (name "unconnected-(J1-Pad113)") (class "Default")
      (node (ref "J1") (pin "113") (pinfunction "113_113") (pintype "passive"))
    )
    (net (code "121") (name "unconnected-(J1-Pad114)") (class "Default")
      (node (ref "J1") (pin "114") (pinfunction "114_114") (pintype "passive"))
    )
    (net (code "122") (name "unconnected-(J1-Pad115)") (class "Default")
      (node (ref "J1") (pin "115") (pinfunction "115_115") (pintype "passive"))
    )
    (net (code "123") (name "unconnected-(J1-Pad116)") (class "Default")
      (node (ref "J1") (pin "116") (pinfunction "116_116") (pintype "passive"))
    )
    (net (code "124") (name "unconnected-(J1-Pad117)") (class "Default")
      (node (ref "J1") (pin "117") (pinfunction "117_117") (pintype "passive"))
    )
    (net (code "125") (name "unconnected-(J1-Pad118)") (class "Default")
      (node (ref "J1") (pin "118") (pinfunction "118_118") (pintype "passive"))
    )
    (net (code "126") (name "unconnected-(J1-Pad119)") (class "Default")
      (node (ref "J1") (pin "119") (pinfunction "119_119") (pintype "passive"))
    )
    (net (code "127") (name "unconnected-(J2-Pad14)") (class "Default")
      (node (ref "J2") (pin "14") (pinfunction "14_14") (pintype "passive"))
    )
  )
)
